# 06_CANBUS.net
KiCad netlist of a schematic drawn in Altium Designer
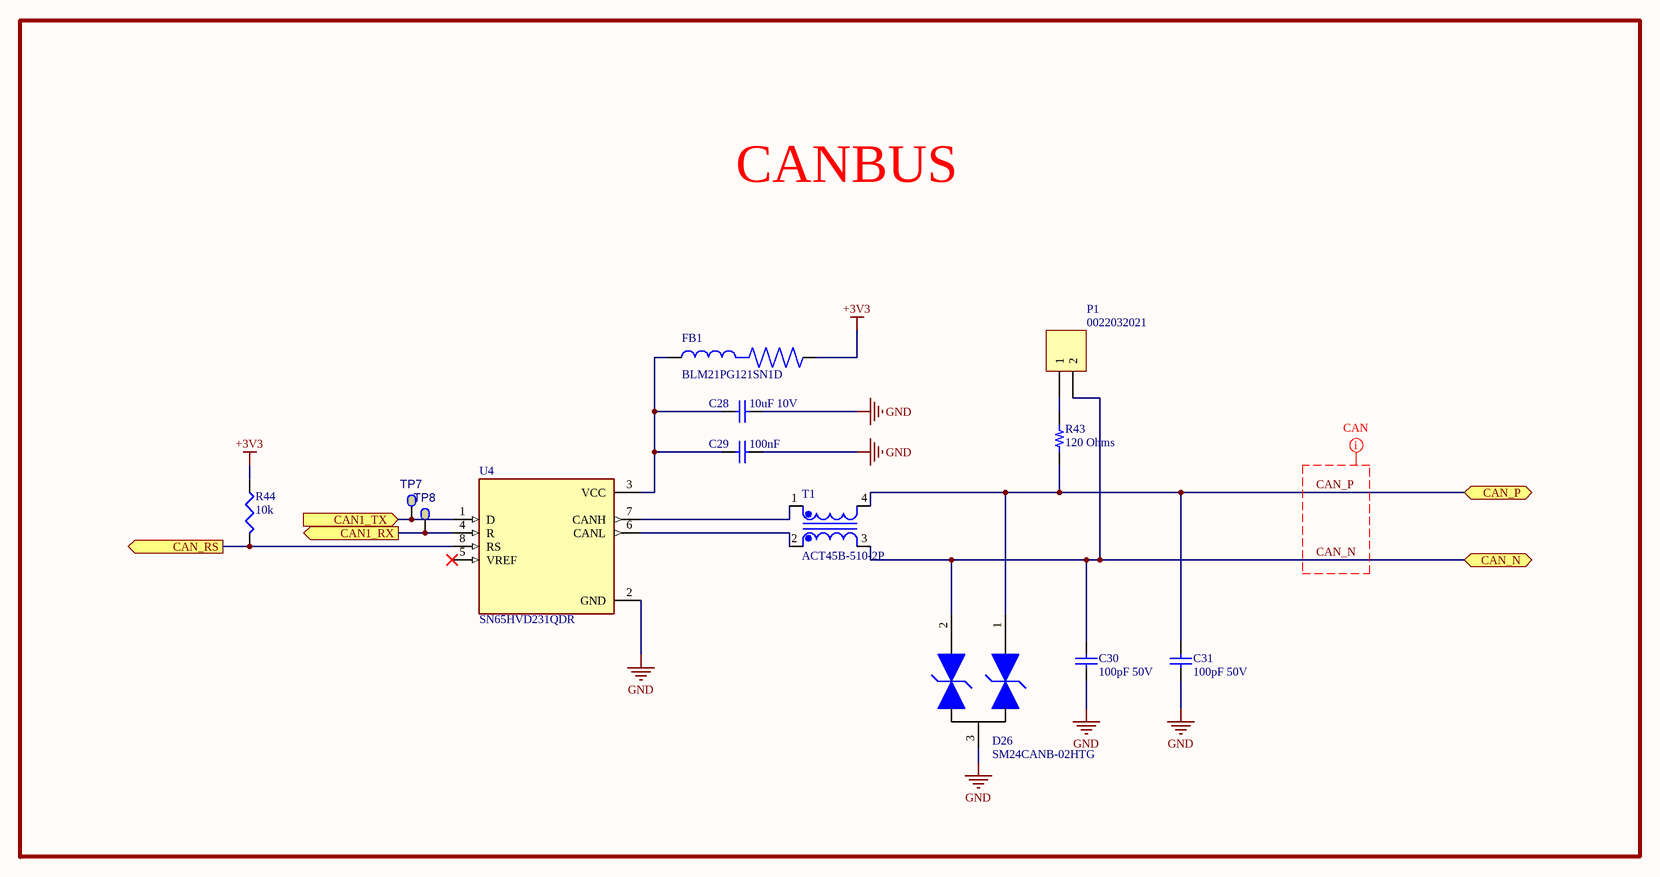
[diagram p0: 06_CANBUS.SchDoc]

(export (version "E")
  (design (tool "Eeschema 10.0.6"))
  (components
    (comp (ref "C28")
      (value "10uF 10V")
      (footprint "SMC0603")
      (description "10 µF ±10% 10V Ceramic Capacitor X5R 0603 (1608 Metric)")
      (fields
        (field (name "MANUFACTURER PART NUMBER") "CL10A106KP8NNNC")
        (field (name "LCSC PART NUMBER") "C19702")
      )
      (libsource (lib "HW_ADHERENT_LANECTRL_R1") (part "CAP0603_10UF_10V"))
    )
    (comp (ref "C29")
      (value "100nF")
      (footprint "CAP0603")
      (description "0.1 µF ±10% 50V Ceramic Capacitor X7R 0603 (1608 Metric)")
      (fields (field (name "MANUFACTURER PART NUMBER") "C0603C104K5RAC7867"))
      (libsource (lib "HW_ADHERENT_LANECTRL_R1") (part "CAP0603_100nF_50V"))
    )
    (comp (ref "C30")
      (value "100pF 50V")
      (footprint "CAP0603")
      (description "100 pF ±5% 50V Ceramic Capacitor C0G, NP0 0603 (1608 Metric)")
      (fields
        (field (name "MANUFACTURER PART NUMBER") "CL10C101JB8NNNC")
        (field (name "LCSC PART NUMBER") "C14858")
      )
      (libsource (lib "HW_ADHERENT_LANECTRL_R1") (part "CAP0603_100PF"))
    )
    (comp (ref "C31")
      (value "100pF 50V")
      (footprint "CAP0603")
      (description "100 pF ±5% 50V Ceramic Capacitor C0G, NP0 0603 (1608 Metric)")
      (fields
        (field (name "MANUFACTURER PART NUMBER") "CL10C101JB8NNNC")
        (field (name "LCSC PART NUMBER") "C14858")
      )
      (libsource (lib "HW_ADHERENT_LANECTRL_R1") (part "CAP0603_100PF"))
    )
    (comp (ref "D26")
      (value "CAN")
      (footprint "SOT23_3-DIODE")
      (description "TVS DIODE 24VWM 50VC SOT23-3")
      (fields
        (field (name "LCSC MANUFACTURER PART NUMBER") "SM24CANB-02HTG")
        (field (name "LCSC PART NUMBER") "C151237")
        (field (name "MANUFACTURER PART NUMBER") "SM24CANB-02HTG")
      )
      (libsource (lib "HW_ADHERENT_LANECTRL_R1") (part "SM24CANB-02HTG_TVS"))
    )
    (comp (ref "FB1")
      (value "BLM21PG121SN1D")
      (footprint "BEADC2012X105N/")
      (description "120 Ohms @ 100 MHz 1 Power Line Ferrite Bead 0805 (2012 Metric) 3A 30mOhm")
      (libsource (lib "HW_ADHERENT_LANECTRL_R1") (part "BLM21PG121SN1D"))
    )
    (comp (ref "P1")
      (value "0022032021")
      (footprint "THD 1x2p. male straight")
      (description "CONN HEADER VERT 2POS 2.54MM")
      (fields (field (name "MANUFACTURER") "Molex"))
      (libsource (lib "HW_ADHERENT_LANECTRL_R1") (part "Header 2"))
    )
    (comp (ref "R43")
      (value "120 Ohms")
      (footprint "RES 1206_3216")
      (description "RES SMD 120 OHM 1% 1/4W 1206")
      (fields (field (name "PART NUMBER") "AC1206FR-07120RL") (field (name "MANUFACTURER") "Yageo"))
      (libsource (lib "HW_ADHERENT_LANECTRL_R1") (part "AC1206FR-07120RL"))
    )
    (comp (ref "R44")
      (value "10k")
      (footprint "RES0603")
      (description "10 kOhms ±1% 0.125W, 1/8W Chip Resistor 0603 (1608 Metric) Anti-Sulfur Thin Film")
      (fields
        (field (name "MANUFACTURER PART NUMBER") "RNCP0603FTD10K0")
        (field (name "LCSC PART NUMBER") "C161803")
      )
      (libsource (lib "HW_ADHERENT_LANECTRL_R1") (part "RES0603_10K_%1_1"))
    )
    (comp (ref "T1")
      (value "ACT45B-510-2P")
      (footprint "TDK_ACT45B-510-2P-TL003_0")
      (description "Ind Common Mode Filter Wirewound 51uH 2KOhm -30% to 50% 100KHz 200mA 1812 T/R")
      (fields
        (field (name "MANUFACTURER") "TDK")
        (field (name "MANUFACTURER PART NUMBER") "ACT45B-510-2P-TL003")
      )
      (libsource (lib "HW_ADHERENT_LANECTRL_R1") (part "ACT45B-510-2P"))
    )
    (comp (ref "TP7")
      (value "Testpoint")
      (footprint "SMD_Ø1.5mm")
      (libsource (lib "HW_ADHERENT_LANECTRL_R1") (part "TEST PAD SMT 10MIL X 20MIL"))
    )
    (comp (ref "TP8")
      (value "Testpoint")
      (footprint "SMD_Ø1.5mm")
      (libsource (lib "HW_ADHERENT_LANECTRL_R1") (part "TEST PAD SMT 10MIL X 20MIL"))
    )
    (comp (ref "U4")
      (value "SN65HVD231QDR")
      (footprint "SOIC127P599X175-8N/")
      (description "3.3-V CAN Transceiver with Sleep Mode")
      (libsource (lib "HW_ADHERENT_LANECTRL_R1") (part "SN65HVD231QDR"))
    )
  )
  (nets
    (net (code "1") (name "+3V3") (class "Default")
      (node (ref "FB1") (pin "2") (pinfunction "2_2") (pintype "passive"))
      (node (ref "R44") (pin "1") (pinfunction "1_1") (pintype "passive"))
    )
    (net (code "2") (name "/CAN1_RX") (class "Default")
      (node (ref "TP8") (pin "1") (pinfunction "P1_1") (pintype "passive"))
      (node (ref "U4") (pin "4") (pinfunction "R_4") (pintype "input"))
    )
    (net (code "3") (name "/CAN1_TX") (class "Default")
      (node (ref "TP7") (pin "1") (pinfunction "P1_1") (pintype "passive"))
      (node (ref "U4") (pin "1") (pinfunction "D_1") (pintype "input"))
    )
    (net (code "4") (name "/CAN_N") (class "Default")
      (node (ref "C30") (pin "2") (pinfunction "2_2") (pintype "passive"))
      (node (ref "D26") (pin "2") (pinfunction "2_2") (pintype "passive"))
      (node (ref "P1") (pin "2") (pinfunction "2_2") (pintype "passive"))
      (node (ref "T1") (pin "3") (pinfunction "3_3") (pintype "passive"))
    )
    (net (code "5") (name "/CAN_P") (class "Default")
      (node (ref "C31") (pin "2") (pinfunction "2_2") (pintype "passive"))
      (node (ref "D26") (pin "1") (pinfunction "1_1") (pintype "passive"))
      (node (ref "R43") (pin "1") (pinfunction "1_1") (pintype "passive"))
      (node (ref "T1") (pin "4") (pinfunction "4_4") (pintype "passive"))
    )
    (net (code "6") (name "/CAN_RS") (class "Default")
      (node (ref "R44") (pin "2") (pinfunction "2_2") (pintype "passive"))
      (node (ref "U4") (pin "8") (pinfunction "RS_8") (pintype "input"))
    )
    (net (code "7") (name "GND") (class "Default")
      (node (ref "C28") (pin "1") (pinfunction "1_1") (pintype "passive"))
      (node (ref "C29") (pin "1") (pinfunction "1_1") (pintype "passive"))
      (node (ref "C30") (pin "1") (pinfunction "1_1") (pintype "passive"))
      (node (ref "C31") (pin "1") (pinfunction "1_1") (pintype "passive"))
      (node (ref "D26") (pin "3") (pinfunction "3_3") (pintype "passive"))
      (node (ref "U4") (pin "2") (pinfunction "GND_2") (pintype "power_in"))
    )
    (net (code "8") (name "Net-(P1-Pad1)") (class "Default")
      (node (ref "P1") (pin "1") (pinfunction "1_1") (pintype "passive"))
      (node (ref "R43") (pin "2") (pinfunction "2_2") (pintype "passive"))
    )
    (net (code "9") (name "Net-(U4-CANH)") (class "Default")
      (node (ref "T1") (pin "1") (pinfunction "1_1") (pintype "passive"))
      (node (ref "U4") (pin "7") (pinfunction "CANH_7") (pintype "output"))
    )
    (net (code "10") (name "Net-(U4-CANL)") (class "Default")
      (node (ref "T1") (pin "2") (pinfunction "2_2") (pintype "passive"))
      (node (ref "U4") (pin "6") (pinfunction "CANL_6") (pintype "output"))
    )
    (net (code "11") (name "Net-(U4-VCC)") (class "Default")
      (node (ref "C28") (pin "2") (pinfunction "2_2") (pintype "passive"))
      (node (ref "C29") (pin "2") (pinfunction "2_2") (pintype "passive"))
      (node (ref "FB1") (pin "1") (pinfunction "1_1") (pintype "passive"))
      (node (ref "U4") (pin "3") (pinfunction "VCC_3") (pintype "power_in"))
    )
    (net (code "12") (name "unconnected-(U4-VREF-Pad5)") (class "Default")
      (node (ref "U4") (pin "5") (pinfunction "VREF_5") (pintype "input+no_connect"))
    )
  )
)
